# Schematic.net
KiCad netlist of a schematic drawn in Altium Designer
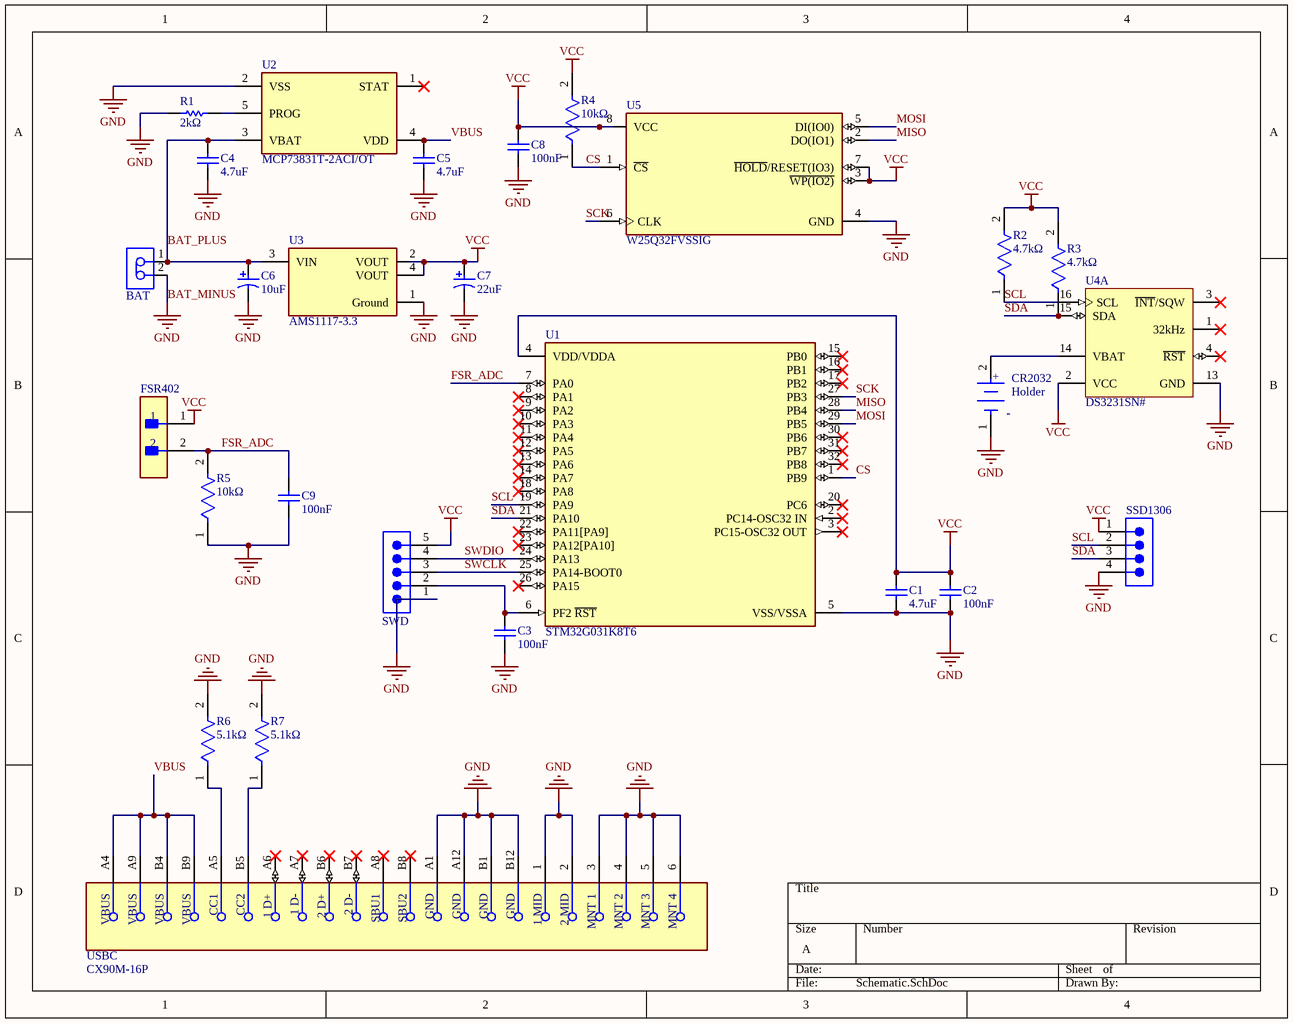
[diagram p0: Schematic.SchDoc]

(export (version "E")
  (design (tool "Eeschema 10.0.6"))
  (components
    (comp (ref "BAT")
      (value "B2B-PH-K-S(LF)(SN)")
      (footprint "JST-B2B-PH-K-S_V")
      (fields (field (name "MANUFACTURER") "JST"))
      (libsource (lib "Altium Content Vault") (part "CN-2P-F-QF2"))
    )
    (comp (ref "C1")
      (value "4.7uF")
      (footprint "CAPC1608X90X35ML15T15")
      (description "C0603C475K9PAC7411")
      (fields (field (name "MANUFACTURER") "Kemet"))
      (libsource (lib "Altium Content Vault") (part "CAP"))
    )
    (comp (ref "C2")
      (value "100nF")
      (footprint "CAPC1608X87X35LL15T15")
      (description "C0603T104K3RACTU")
      (fields (field (name "MANUFACTURER") "Kemet"))
      (libsource (lib "Altium Content Vault") (part "CAP"))
    )
    (comp (ref "C3")
      (value "100nF")
      (footprint "CAPC1608X87X35LL15T15")
      (description "C0603T104K3RACTU")
      (fields (field (name "MANUFACTURER") "Kemet"))
      (libsource (lib "Altium Content Vault") (part "CAP"))
    )
    (comp (ref "C4")
      (value "4.7uF")
      (footprint "CAPC1608X90X35ML15T15")
      (description "C0603C475K9PAC7411")
      (fields (field (name "MANUFACTURER") "Kemet"))
      (libsource (lib "Altium Content Vault") (part "CAP"))
    )
    (comp (ref "C5")
      (value "4.7uF")
      (footprint "CAPC1608X90X35ML15T15")
      (description "C0603C475K9PAC7411")
      (fields (field (name "MANUFACTURER") "Kemet"))
      (libsource (lib "Altium Content Vault") (part "CAP"))
    )
    (comp (ref "C6")
      (value "10uF")
      (footprint "KEMT-T322-2_V")
      (description "T322C106K025AT")
      (fields (field (name "MANUFACTURER") "Kemet") (field (name "TOLERANCE") "-10,+10%"))
      (libsource (lib "Altium Content Vault") (part "CAP-P-2"))
    )
    (comp (ref "C7")
      (value "22uF")
      (footprint "KEMT-T491-B_L")
      (description "T491B226K010AT")
      (fields (field (name "VOLTAGE") "10VDC") (field (name "MANUFACTURER") "Kemet"))
      (libsource (lib "Altium Content Vault") (part "CAP-P-2"))
    )
    (comp (ref "C8")
      (value "100nF")
      (footprint "CAPC1608X87X35LL15T15")
      (description "C0603T104K3RACTU")
      (fields (field (name "MANUFACTURER") "Kemet"))
      (libsource (lib "Altium Content Vault") (part "CAP"))
    )
    (comp (ref "C9")
      (value "100nF")
      (footprint "CAPC1608X87X35LL15T15")
      (description "C0603T104K3RACTU")
      (fields (field (name "MANUFACTURER") "Kemet"))
      (libsource (lib "Altium Content Vault") (part "CAP"))
    )
    (comp (ref "CR2032")
      (value "Holder")
      (footprint "FP-1775485-1-MFG")
      (description "BATT HLDR COIN 20MM 1 CEL PC PIN")
      (libsource (lib "Altium Content Vault") (part "60d3b5b901a8747834971d0eb8cf3fd"))
    )
    (comp (ref "FSR402")
      (value "~")
      (footprint "FP-B02B-WPJSS-1_LF_SN-MFG")
      (description "CONN HEADER VERT 2POS 5MM")
      (libsource (lib "Altium Content Vault") (part "3bc925449376181038e59eaffc5286c"))
    )
    (comp (ref "R1")
      (value "2kΩ")
      (footprint "RESC1608X55X25LL10T15")
      (description "RC0603FR-102KL")
      (fields (field (name "MANUFACTURER") "Yageo"))
      (libsource (lib "Altium Content Vault") (part "RES"))
    )
    (comp (ref "R2")
      (value "4.7kΩ")
      (footprint "FP-RMCF0603-IPC_B")
      (description "RMCF0603FG4K70")
      (fields (field (name "TOLERANCE") "1%"))
      (libsource (lib "Altium Content Vault") (part "1029c3af85768c4190bb7ad29bc67b5"))
    )
    (comp (ref "R3")
      (value "4.7kΩ")
      (footprint "FP-RMCF0603-IPC_B")
      (description "RMCF0603FG4K70")
      (fields (field (name "TOLERANCE") "1%"))
      (libsource (lib "Altium Content Vault") (part "1029c3af85768c4190bb7ad29bc67b5"))
    )
    (comp (ref "R4")
      (value "10kΩ")
      (footprint "FP-AC0603-IPC_A")
      (description "RES 10kΩ 5.00% 0.2W 0603")
      (libsource (lib "Altium Content Vault") (part "1029c3af85768c4190bb7ad29bc67b5"))
    )
    (comp (ref "R5")
      (value "10kΩ")
      (footprint "FP-AC0603-IPC_A")
      (description "RES 10kΩ 5.00% 0.2W 0603")
      (libsource (lib "Altium Content Vault") (part "1029c3af85768c4190bb7ad29bc67b5"))
    )
    (comp (ref "R6")
      (value "5.1kΩ")
      (footprint "FP-MCR03-IPC_B")
      (description "MCR03EZPJ512")
      (fields (field (name "TOLERANCE") "5%"))
      (libsource (lib "Altium Content Vault") (part "1029c3af85768c4190bb7ad29bc67b5"))
    )
    (comp (ref "R7")
      (value "5.1kΩ")
      (footprint "FP-MCR03-IPC_B")
      (description "MCR03EZPJ512")
      (fields (field (name "TOLERANCE") "5%"))
      (libsource (lib "Altium Content Vault") (part "1029c3af85768c4190bb7ad29bc67b5"))
    )
    (comp (ref "SSD1306")
      (value "691317710004")
      (footprint "691317710004")
      (description "Terminal Block, 5.00MM Pitch, Close Horizontal Pcb Header, Flanges, 4 Pins")
      (libsource (lib "Altium Content Vault") (part "TBL - 1R - 04P - Male"))
    )
    (comp (ref "SWD")
      (value "691305330005")
      (footprint "691305330005")
      (description "Terminal Block, Header, 5Pos, Th Rohs Compliant: Yes")
      (libsource (lib "Altium Content Vault") (part "TBL - 1R - 05P - Male"))
    )
    (comp (ref "U1")
      (value "STM32G031K8T6")
      (footprint "FP-LQFP32-5V-MFG")
      (description "IC MCU 32BIT 64KB FLASH 32LQFP")
      (libsource (lib "Altium Content Vault") (part "473aa7f4ee034338f9424f96f5febff"))
    )
    (comp (ref "U2")
      (value "MCP73831T-2ACI/OT")
      (footprint "FP-C04-091-OT-IPC_B")
      (description "IC CONTROLLR LI-ION 4.2V SOT23-5")
      (libsource (lib "Altium Content Vault") (part "61f5a3bb3429d9e0caadea342aa3b19"))
    )
    (comp (ref "U3")
      (value "AMS1117-3.3")
      (footprint "FP-AMS1117-IPC_C")
      (description "LDO Voltage Regulators 1A, 3.3V")
      (fields
        (field (name "OCTOPART") "https://octopart.com/ams1117-3.3-advanced+monolithic+systems-25899300")
        (field (name "MANUFACTURER") "Advanced Monolithic Systems")
      )
      (libsource (lib "Altium Content Vault") (part "8bdbb5f8e77002000e30dd2845d0354"))
    )
    (comp (ref "U4")
      (value "DS3231SN#")
      (footprint "W16#H2_L")
      (libsource (lib "Altium Content Vault") (part "MAX-RTC-16-DS3231S-W16#H2"))
    )
    (comp (ref "U5")
      (value "W25Q32FVSSIG")
      (footprint "FP-SS-MFG")
      (description "IC FLASH 32M SPI 104MHZ 8SOIC")
      (fields
        (field (name "MANUFACTURER") "Winbond")
        (field (name "OCTOPART") "https://octopart.com/w25q32fvssig-winbond-23896462")
      )
      (libsource (lib "Altium Content Vault") (part "4804fbe011262506d6ec6a9051036b0"))
    )
    (comp (ref "USBC")
      (value "CX90M-16P")
      (footprint "FP-CX90M-16P-MFG")
      (description "CONN RCPT USB2.0 TYPEC 16POS SMD")
      (libsource (lib "Altium Content Vault") (part "6b7e9819a715c2d1d3babe584a73dea"))
    )
  )
  (nets
    (net (code "1") (name "/BAT_PLUS") (class "Default")
      (node (ref "BAT") (pin "1") (pinfunction "1_1") (pintype "passive"))
      (node (ref "C4") (pin "2") (pinfunction "2_2") (pintype "passive"))
      (node (ref "C6") (pin "1") (pinfunction "1_1") (pintype "passive"))
      (node (ref "U2") (pin "3") (pinfunction "VBAT_3") (pintype "power_in"))
      (node (ref "U3") (pin "3") (pinfunction "VIN_3") (pintype "power_in"))
    )
    (net (code "2") (name "/CS") (class "Default")
      (node (ref "R4") (pin "1") (pinfunction "1_1") (pintype "passive"))
      (node (ref "U1") (pin "1") (pinfunction "PB9_1") (pintype "bidirectional"))
      (node (ref "U5") (pin "1") (pinfunction "~{CS}_1") (pintype "input"))
    )
    (net (code "3") (name "/FSR_ADC") (class "Default")
      (node (ref "C9") (pin "2") (pinfunction "2_2") (pintype "passive"))
      (node (ref "FSR402") (pin "2") (pinfunction "2_2") (pintype "passive"))
      (node (ref "R5") (pin "2") (pinfunction "2_2") (pintype "passive"))
      (node (ref "U1") (pin "7") (pinfunction "PA0_7") (pintype "bidirectional"))
    )
    (net (code "4") (name "/MISO") (class "Default")
      (node (ref "U1") (pin "28") (pinfunction "PB4_28") (pintype "bidirectional"))
      (node (ref "U5") (pin "2") (pinfunction "DO(IO1)_2") (pintype "bidirectional"))
    )
    (net (code "5") (name "/MOSI") (class "Default")
      (node (ref "U1") (pin "29") (pinfunction "PB5_29") (pintype "bidirectional"))
      (node (ref "U5") (pin "5") (pinfunction "DI(IO0)_5") (pintype "bidirectional"))
    )
    (net (code "6") (name "/SCK") (class "Default")
      (node (ref "U1") (pin "27") (pinfunction "PB3_27") (pintype "bidirectional"))
      (node (ref "U5") (pin "6") (pinfunction "CLK_6") (pintype "input"))
    )
    (net (code "7") (name "/SCL") (class "Default")
      (node (ref "R2") (pin "1") (pinfunction "1_1") (pintype "passive"))
      (node (ref "SSD1306") (pin "2") (pinfunction "2_2") (pintype "passive"))
      (node (ref "U1") (pin "19") (pinfunction "PA9_19") (pintype "bidirectional"))
      (node (ref "U4") (pin "16") (pinfunction "SCL_16") (pintype "input"))
    )
    (net (code "8") (name "/SDA") (class "Default")
      (node (ref "R3") (pin "1") (pinfunction "1_1") (pintype "passive"))
      (node (ref "SSD1306") (pin "3") (pinfunction "3_3") (pintype "passive"))
      (node (ref "U1") (pin "21") (pinfunction "PA10_21") (pintype "bidirectional"))
      (node (ref "U4") (pin "15") (pinfunction "SDA_15") (pintype "bidirectional"))
    )
    (net (code "9") (name "/SWCLK") (class "Default")
      (node (ref "SWD") (pin "3") (pinfunction "3_3") (pintype "passive"))
      (node (ref "U1") (pin "25") (pinfunction "PA14-BOOT0_25") (pintype "bidirectional"))
    )
    (net (code "10") (name "/SWDIO") (class "Default")
      (node (ref "SWD") (pin "4") (pinfunction "4_4") (pintype "passive"))
      (node (ref "U1") (pin "24") (pinfunction "PA13_24") (pintype "bidirectional"))
    )
    (net (code "11") (name "/VBUS") (class "Default")
      (node (ref "C5") (pin "2") (pinfunction "2_2") (pintype "passive"))
      (node (ref "U2") (pin "4") (pinfunction "VDD_4") (pintype "power_in"))
      (node (ref "USBC") (pin "A4") (pinfunction "VBUS_A4") (pintype "power_in"))
      (node (ref "USBC") (pin "A9") (pinfunction "VBUS_A9") (pintype "power_in"))
      (node (ref "USBC") (pin "B4") (pinfunction "VBUS_B4") (pintype "power_in"))
      (node (ref "USBC") (pin "B9") (pinfunction "VBUS_B9") (pintype "power_in"))
    )
    (net (code "12") (name "GND") (class "Default")
      (node (ref "BAT") (pin "2") (pinfunction "2_2") (pintype "passive"))
      (node (ref "C1") (pin "1") (pinfunction "1_1") (pintype "passive"))
      (node (ref "C2") (pin "1") (pinfunction "1_1") (pintype "passive"))
      (node (ref "C3") (pin "2") (pinfunction "2_2") (pintype "passive"))
      (node (ref "C4") (pin "1") (pinfunction "1_1") (pintype "passive"))
      (node (ref "C5") (pin "1") (pinfunction "1_1") (pintype "passive"))
      (node (ref "C6") (pin "2") (pinfunction "2_2") (pintype "passive"))
      (node (ref "C7") (pin "2") (pinfunction "2_2") (pintype "passive"))
      (node (ref "C8") (pin "1") (pinfunction "1_1") (pintype "passive"))
      (node (ref "C9") (pin "1") (pinfunction "1_1") (pintype "passive"))
      (node (ref "CR2032") (pin "1") (pinfunction "C_1") (pintype "passive"))
      (node (ref "R1") (pin "1") (pinfunction "1_1") (pintype "passive"))
      (node (ref "R5") (pin "1") (pinfunction "1_1") (pintype "passive"))
      (node (ref "R6") (pin "2") (pinfunction "2_2") (pintype "passive"))
      (node (ref "R7") (pin "2") (pinfunction "2_2") (pintype "passive"))
      (node (ref "SSD1306") (pin "4") (pinfunction "4_4") (pintype "passive"))
      (node (ref "SWD") (pin "1") (pinfunction "1_1") (pintype "passive"))
      (node (ref "U1") (pin "5") (pinfunction "VSS/VSSA_5") (pintype "power_in"))
      (node (ref "U2") (pin "2") (pinfunction "VSS_2") (pintype "power_in"))
      (node (ref "U3") (pin "1") (pinfunction "Ground_1") (pintype "power_in"))
      (node (ref "U4") (pin "13") (pinfunction "GND_13") (pintype "power_in"))
      (node (ref "U5") (pin "4") (pinfunction "GND_4") (pintype "power_in"))
      (node (ref "USBC") (pin "1") (pinfunction "1_MID_1") (pintype "passive"))
      (node (ref "USBC") (pin "2") (pinfunction "2_MID_2") (pintype "passive"))
      (node (ref "USBC") (pin "3") (pinfunction "MNT_1_3") (pintype "passive"))
      (node (ref "USBC") (pin "4") (pinfunction "MNT_2_4") (pintype "passive"))
      (node (ref "USBC") (pin "5") (pinfunction "MNT_3_5") (pintype "passive"))
      (node (ref "USBC") (pin "6") (pinfunction "MNT_4_6") (pintype "passive"))
      (node (ref "USBC") (pin "A1") (pinfunction "GND_A1") (pintype "power_in"))
      (node (ref "USBC") (pin "A12") (pinfunction "GND_A12") (pintype "power_in"))
      (node (ref "USBC") (pin "B1") (pinfunction "GND_B1") (pintype "power_in"))
      (node (ref "USBC") (pin "B12") (pinfunction "GND_B12") (pintype "power_in"))
    )
    (net (code "13") (name "Net-(CR2032-A)") (class "Default")
      (node (ref "CR2032") (pin "2") (pinfunction "A_2") (pintype "passive"))
      (node (ref "U4") (pin "14") (pinfunction "VBAT_14") (pintype "power_in"))
    )
    (net (code "14") (name "Net-(U1-PF2_~{RST})") (class "Default")
      (node (ref "C3") (pin "1") (pinfunction "1_1") (pintype "passive"))
      (node (ref "SWD") (pin "2") (pinfunction "2_2") (pintype "passive"))
      (node (ref "U1") (pin "6") (pinfunction "PF2_~{RST}_6") (pintype "input"))
    )
    (net (code "15") (name "Net-(U2-PROG)") (class "Default")
      (node (ref "R1") (pin "2") (pinfunction "2_2") (pintype "passive"))
      (node (ref "U2") (pin "5") (pinfunction "PROG_5") (pintype "passive"))
    )
    (net (code "16") (name "Net-(USBC-CC1)") (class "Default")
      (node (ref "R6") (pin "1") (pinfunction "1_1") (pintype "passive"))
      (node (ref "USBC") (pin "A5") (pinfunction "CC1_A5") (pintype "passive"))
    )
    (net (code "17") (name "Net-(USBC-CC2)") (class "Default")
      (node (ref "R7") (pin "1") (pinfunction "1_1") (pintype "passive"))
      (node (ref "USBC") (pin "B5") (pinfunction "CC2_B5") (pintype "passive"))
    )
    (net (code "18") (name "VCC") (class "Default")
      (node (ref "C1") (pin "2") (pinfunction "2_2") (pintype "passive"))
      (node (ref "C2") (pin "2") (pinfunction "2_2") (pintype "passive"))
      (node (ref "C7") (pin "1") (pinfunction "1_1") (pintype "passive"))
      (node (ref "C8") (pin "2") (pinfunction "2_2") (pintype "passive"))
      (node (ref "FSR402") (pin "1") (pinfunction "1_1") (pintype "passive"))
      (node (ref "R2") (pin "2") (pinfunction "2_2") (pintype "passive"))
      (node (ref "R3") (pin "2") (pinfunction "2_2") (pintype "passive"))
      (node (ref "R4") (pin "2") (pinfunction "2_2") (pintype "passive"))
      (node (ref "SSD1306") (pin "1") (pinfunction "1_1") (pintype "passive"))
      (node (ref "SWD") (pin "5") (pinfunction "5_5") (pintype "passive"))
      (node (ref "U1") (pin "4") (pinfunction "VDD/VDDA_4") (pintype "power_in"))
      (node (ref "U3") (pin "2") (pinfunction "VOUT_2") (pintype "passive"))
      (node (ref "U3") (pin "4") (pinfunction "VOUT_4") (pintype "passive"))
      (node (ref "U4") (pin "2") (pinfunction "VCC_2") (pintype "power_in"))
      (node (ref "U5") (pin "3") (pinfunction "~{WP(IO2)}_3") (pintype "bidirectional"))
      (node (ref "U5") (pin "7") (pinfunction "~{HOLD}/RESET(IO3)_7") (pintype "bidirectional"))
      (node (ref "U5") (pin "8") (pinfunction "VCC_8") (pintype "power_in"))
    )
    (net (code "19") (name "unconnected-(U1-PA1-Pad8)") (class "Default")
      (node (ref "U1") (pin "8") (pinfunction "PA1_8") (pintype "bidirectional+no_connect"))
    )
    (net (code "20") (name "unconnected-(U1-PA2-Pad9)") (class "Default")
      (node (ref "U1") (pin "9") (pinfunction "PA2_9") (pintype "bidirectional+no_connect"))
    )
    (net (code "21") (name "unconnected-(U1-PA3-Pad10)") (class "Default")
      (node (ref "U1") (pin "10") (pinfunction "PA3_10") (pintype "bidirectional+no_connect"))
    )
    (net (code "22") (name "unconnected-(U1-PA4-Pad11)") (class "Default")
      (node (ref "U1") (pin "11") (pinfunction "PA4_11") (pintype "bidirectional+no_connect"))
    )
    (net (code "23") (name "unconnected-(U1-PA5-Pad12)") (class "Default")
      (node (ref "U1") (pin "12") (pinfunction "PA5_12") (pintype "bidirectional+no_connect"))
    )
    (net (code "24") (name "unconnected-(U1-PA6-Pad13)") (class "Default")
      (node (ref "U1") (pin "13") (pinfunction "PA6_13") (pintype "bidirectional+no_connect"))
    )
    (net (code "25") (name "unconnected-(U1-PA7-Pad14)") (class "Default")
      (node (ref "U1") (pin "14") (pinfunction "PA7_14") (pintype "bidirectional+no_connect"))
    )
    (net (code "26") (name "unconnected-(U1-PA8-Pad18)") (class "Default")
      (node (ref "U1") (pin "18") (pinfunction "PA8_18") (pintype "bidirectional+no_connect"))
    )
    (net (code "27") (name "unconnected-(U1-PA11[PA9]-Pad22)") (class "Default")
      (node (ref "U1") (pin "22") (pinfunction "PA11[PA9]_22") (pintype "bidirectional+no_connect"))
    )
    (net (code "28") (name "unconnected-(U1-PA12[PA10]-Pad23)") (class "Default")
      (node (ref "U1") (pin "23") (pinfunction "PA12[PA10]_23") (pintype "bidirectional+no_connect"))
    )
    (net (code "29") (name "unconnected-(U1-PA15-Pad26)") (class "Default")
      (node (ref "U1") (pin "26") (pinfunction "PA15_26") (pintype "bidirectional+no_connect"))
    )
    (net (code "30") (name "unconnected-(U1-PB0-Pad15)") (class "Default")
      (node (ref "U1") (pin "15") (pinfunction "PB0_15") (pintype "bidirectional+no_connect"))
    )
    (net (code "31") (name "unconnected-(U1-PB1-Pad16)") (class "Default")
      (node (ref "U1") (pin "16") (pinfunction "PB1_16") (pintype "bidirectional+no_connect"))
    )
    (net (code "32") (name "unconnected-(U1-PB2-Pad17)") (class "Default")
      (node (ref "U1") (pin "17") (pinfunction "PB2_17") (pintype "bidirectional+no_connect"))
    )
    (net (code "33") (name "unconnected-(U1-PB6-Pad30)") (class "Default")
      (node (ref "U1") (pin "30") (pinfunction "PB6_30") (pintype "bidirectional+no_connect"))
    )
    (net (code "34") (name "unconnected-(U1-PB7-Pad31)") (class "Default")
      (node (ref "U1") (pin "31") (pinfunction "PB7_31") (pintype "bidirectional+no_connect"))
    )
    (net (code "35") (name "unconnected-(U1-PB8-Pad32)") (class "Default")
      (node (ref "U1") (pin "32") (pinfunction "PB8_32") (pintype "bidirectional+no_connect"))
    )
    (net (code "36") (name "unconnected-(U1-PC6-Pad20)") (class "Default")
      (node (ref "U1") (pin "20") (pinfunction "PC6_20") (pintype "bidirectional+no_connect"))
    )
    (net (code "37") (name "unconnected-(U1-PC14-OSC32_IN-Pad2)") (class "Default")
      (node (ref "U1") (pin "2") (pinfunction "PC14-OSC32_IN_2") (pintype "input+no_connect"))
    )
    (net (code "38") (name "unconnected-(U1-PC15-OSC32_OUT-Pad3)") (class "Default")
      (node (ref "U1") (pin "3") (pinfunction "PC15-OSC32_OUT_3") (pintype "output+no_connect"))
    )
    (net (code "39") (name "unconnected-(U2-STAT-Pad1)") (class "Default")
      (node (ref "U2") (pin "1") (pinfunction "STAT_1") (pintype "passive+no_connect"))
    )
    (net (code "40") (name "unconnected-(U4A-32kHz-Pad1)") (class "Default")
      (node (ref "U4") (pin "1") (pinfunction "32kHz_1") (pintype "open_collector+no_connect"))
    )
    (net (code "41") (name "unconnected-(U4A-~{INT}{slash}SQW-Pad3)") (class "Default")
      (node (ref "U4") (pin "3") (pinfunction "~{INT}/SQW_3") (pintype "open_collector+no_connect"))
    )
    (net (code "42") (name "unconnected-(U4A-~{RST}-Pad4)") (class "Default")
      (node (ref "U4") (pin "4") (pinfunction "~{RST}_4") (pintype "bidirectional+no_connect"))
    )
    (net (code "43") (name "unconnected-(USBC-1_D+-PadA6)") (class "Default")
      (node (ref "USBC") (pin "A6") (pinfunction "1_D+_A6") (pintype "bidirectional+no_connect"))
    )
    (net (code "44") (name "unconnected-(USBC-1_D--PadA7)") (class "Default")
      (node (ref "USBC") (pin "A7") (pinfunction "1_D-_A7") (pintype "bidirectional+no_connect"))
    )
    (net (code "45") (name "unconnected-(USBC-2_D+-PadB6)") (class "Default")
      (node (ref "USBC") (pin "B6") (pinfunction "2_D+_B6") (pintype "bidirectional+no_connect"))
    )
    (net (code "46") (name "unconnected-(USBC-2_D--PadB7)") (class "Default")
      (node (ref "USBC") (pin "B7") (pinfunction "2_D-_B7") (pintype "bidirectional+no_connect"))
    )
    (net (code "47") (name "unconnected-(USBC-SBU1-PadA8)") (class "Default")
      (node (ref "USBC") (pin "A8") (pinfunction "SBU1_A8") (pintype "passive+no_connect"))
    )
    (net (code "48") (name "unconnected-(USBC-SBU2-PadB8)") (class "Default")
      (node (ref "USBC") (pin "B8") (pinfunction "SBU2_B8") (pintype "passive+no_connect"))
    )
  )
)
